# audio_pa6.net
KiCad netlist of a schematic drawn in Altium Designer
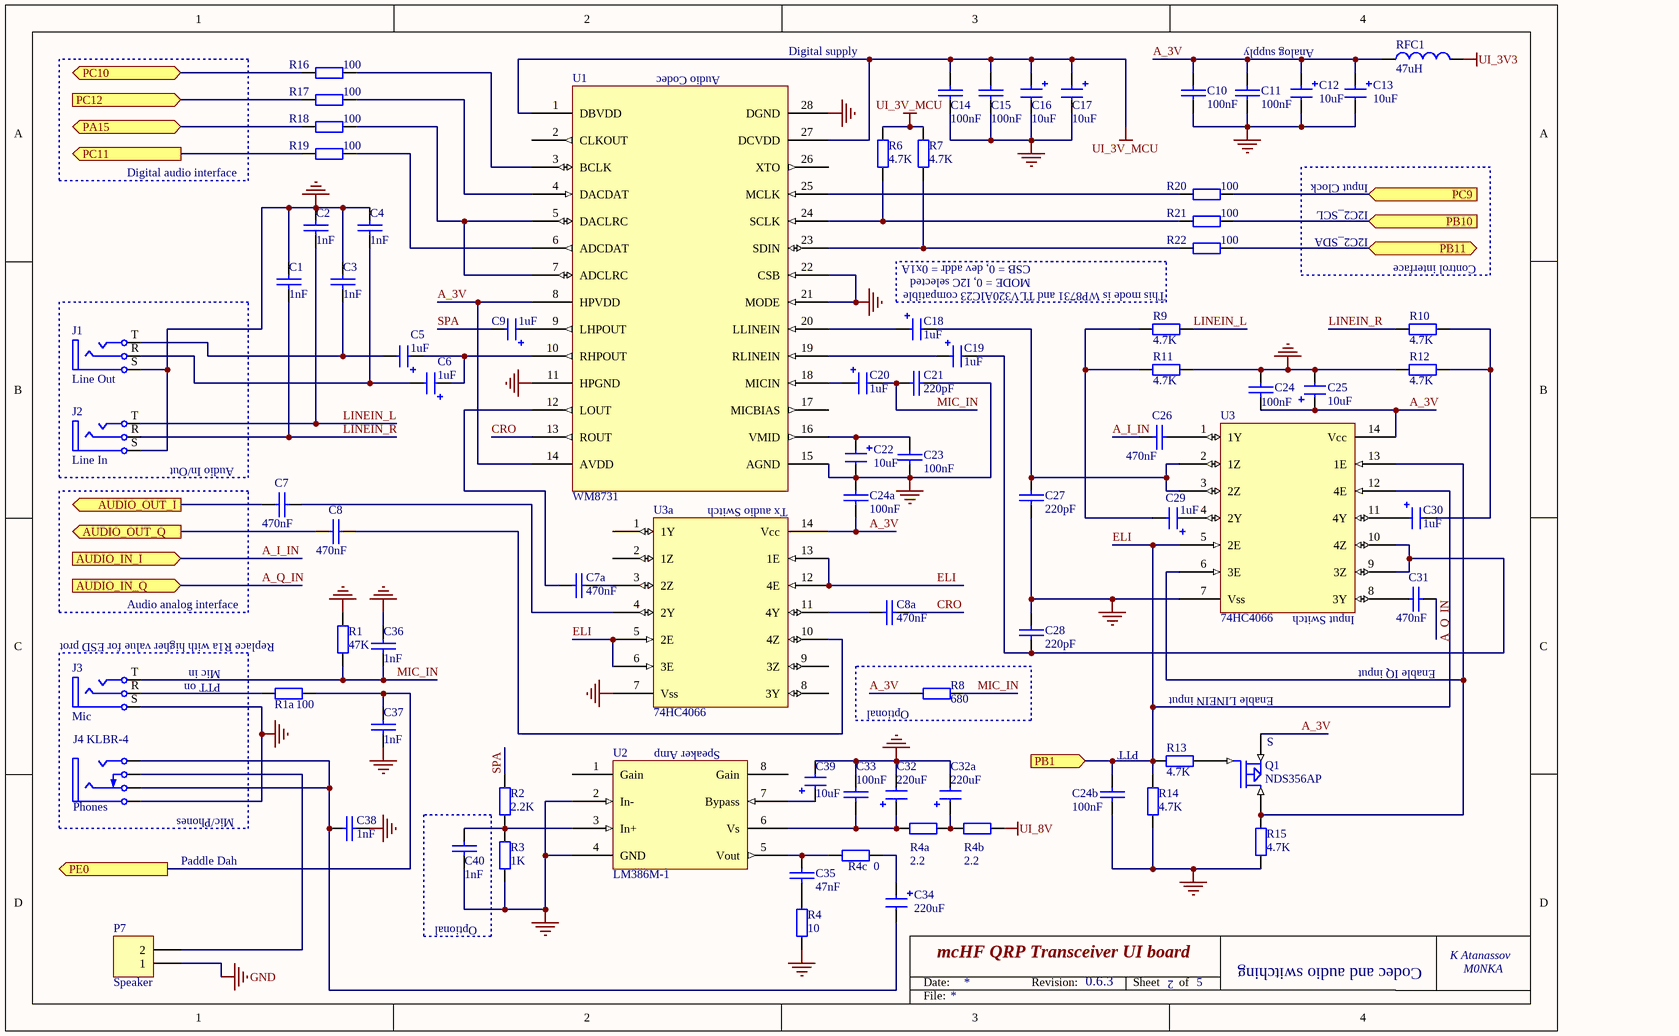
[diagram p0: audio_pa6.SchDoc]

(export (version "E")
  (design (tool "Eeschema 10.0.6"))
  (components
    (comp (ref "C1")
      (value "1nF")
      (footprint "0805-Pro")
      (description "Capacitor")
      (libsource (lib "mcHF_ui") (part "CAP"))
    )
    (comp (ref "C2")
      (value "1nF")
      (footprint "0805-Pro")
      (description "Capacitor")
      (libsource (lib "mcHF_ui") (part "CAP"))
    )
    (comp (ref "C3")
      (value "1nF")
      (footprint "0805-Pro")
      (description "Capacitor")
      (libsource (lib "mcHF_ui") (part "CAP"))
    )
    (comp (ref "C4")
      (value "1nF")
      (footprint "0805-Pro")
      (description "Capacitor")
      (libsource (lib "mcHF_ui") (part "CAP"))
    )
    (comp (ref "C5")
      (value "1uF")
      (footprint "1206_ELEC_CAP_N")
      (description "Electrolitic capacitor")
      (libsource (lib "mcHF_ui") (part "CAP-POL"))
    )
    (comp (ref "C6")
      (value "1uF")
      (footprint "1206_ELEC_CAP_N")
      (description "Electrolitic capacitor")
      (libsource (lib "mcHF_ui") (part "CAP-POL"))
    )
    (comp (ref "C7")
      (value "470nF")
      (footprint "0805-Pro")
      (description "Capacitor")
      (libsource (lib "mcHF_ui") (part "CAP"))
    )
    (comp (ref "C7a")
      (value "470nF")
      (footprint "0805-Pro")
      (description "Capacitor")
      (libsource (lib "mcHF_ui") (part "CAP"))
    )
    (comp (ref "C8")
      (value "470nF")
      (footprint "0805-Pro")
      (description "Capacitor")
      (libsource (lib "mcHF_ui") (part "CAP"))
    )
    (comp (ref "C8a")
      (value "470nF")
      (footprint "0805-Pro")
      (description "Capacitor")
      (libsource (lib "mcHF_ui") (part "CAP"))
    )
    (comp (ref "C9")
      (value "1uF")
      (footprint "1206_ELEC_CAP_N")
      (description "Electrolitic capacitor")
      (libsource (lib "mcHF_ui") (part "CAP-POL"))
    )
    (comp (ref "C10")
      (value "100nF")
      (footprint "0805-Pro")
      (description "Capacitor")
      (libsource (lib "mcHF_ui") (part "CAP"))
    )
    (comp (ref "C11")
      (value "100nF")
      (footprint "0805-Pro")
      (description "Capacitor")
      (libsource (lib "mcHF_ui") (part "CAP"))
    )
    (comp (ref "C12")
      (value "10uF")
      (footprint "1206_ELEC_CAP_N")
      (description "Electrolitic capacitor")
      (libsource (lib "mcHF_ui") (part "CAP-POL"))
    )
    (comp (ref "C13")
      (value "10uF")
      (footprint "1206_ELEC_CAP_N")
      (description "Electrolitic capacitor")
      (libsource (lib "mcHF_ui") (part "CAP-POL"))
    )
    (comp (ref "C14")
      (value "100nF")
      (footprint "0805-Pro")
      (description "Capacitor")
      (libsource (lib "mcHF_ui") (part "CAP"))
    )
    (comp (ref "C15")
      (value "100nF")
      (footprint "0805-Pro")
      (description "Capacitor")
      (libsource (lib "mcHF_ui") (part "CAP"))
    )
    (comp (ref "C16")
      (value "10uF")
      (footprint "1206_ELEC_CAP_N")
      (description "Electrolitic capacitor")
      (libsource (lib "mcHF_ui") (part "CAP-POL"))
    )
    (comp (ref "C17")
      (value "10uF")
      (footprint "1206_ELEC_CAP_N")
      (description "Electrolitic capacitor")
      (libsource (lib "mcHF_ui") (part "CAP-POL"))
    )
    (comp (ref "C18")
      (value "1uF")
      (footprint "1206_ELEC_CAP_N")
      (description "Electrolitic capacitor")
      (libsource (lib "mcHF_ui") (part "CAP-POL"))
    )
    (comp (ref "C19")
      (value "1uF")
      (footprint "1206_ELEC_CAP_N")
      (description "Electrolitic capacitor")
      (libsource (lib "mcHF_ui") (part "CAP-POL"))
    )
    (comp (ref "C20")
      (value "1uF")
      (footprint "1206_ELEC_CAP_N")
      (description "Electrolitic capacitor")
      (libsource (lib "mcHF_ui") (part "CAP-POL"))
    )
    (comp (ref "C21")
      (value "220pF")
      (footprint "0805-Pro")
      (description "Capacitor")
      (libsource (lib "mcHF_ui") (part "CAP"))
    )
    (comp (ref "C22")
      (value "10uF")
      (footprint "1206_ELEC_CAP_N")
      (description "Electrolitic capacitor")
      (libsource (lib "mcHF_ui") (part "CAP-POL"))
    )
    (comp (ref "C23")
      (value "100nF")
      (footprint "0805-Pro")
      (description "Capacitor")
      (libsource (lib "mcHF_ui") (part "CAP"))
    )
    (comp (ref "C24")
      (value "100nF")
      (footprint "0805-Pro")
      (description "Capacitor")
      (libsource (lib "mcHF_ui") (part "CAP"))
    )
    (comp (ref "C24a")
      (value "100nF")
      (footprint "0805-Pro")
      (description "Capacitor")
      (libsource (lib "mcHF_ui") (part "CAP"))
    )
    (comp (ref "C24b")
      (value "100nF")
      (footprint "0805-Pro")
      (description "Capacitor")
      (libsource (lib "mcHF_ui") (part "CAP"))
    )
    (comp (ref "C25")
      (value "10uF")
      (footprint "1206_ELEC_CAP_N")
      (description "Electrolitic capacitor")
      (libsource (lib "mcHF_ui") (part "CAP-POL"))
    )
    (comp (ref "C26")
      (value "470nF")
      (footprint "0805-Pro")
      (description "Capacitor")
      (libsource (lib "mcHF_ui") (part "CAP"))
    )
    (comp (ref "C27")
      (value "220pF")
      (footprint "0805-Pro")
      (description "Capacitor")
      (libsource (lib "mcHF_ui") (part "CAP"))
    )
    (comp (ref "C28")
      (value "220pF")
      (footprint "0805-Pro")
      (description "Capacitor")
      (libsource (lib "mcHF_ui") (part "CAP"))
    )
    (comp (ref "C29")
      (value "1uF")
      (footprint "1206_ELEC_CAP_N")
      (description "Electrolitic capacitor")
      (libsource (lib "mcHF_ui") (part "CAP-POL"))
    )
    (comp (ref "C30")
      (value "1uF")
      (footprint "1206_ELEC_CAP_N")
      (description "Electrolitic capacitor")
      (libsource (lib "mcHF_ui") (part "CAP-POL"))
    )
    (comp (ref "C31")
      (value "470nF")
      (footprint "0805-Pro")
      (description "Capacitor")
      (libsource (lib "mcHF_ui") (part "CAP"))
    )
    (comp (ref "C32")
      (value "220uF")
      (footprint "CAP_ALUM")
      (description "Electrolitic capacitor")
      (libsource (lib "mcHF_ui") (part "CAP-POL"))
    )
    (comp (ref "C32a")
      (value "220uF")
      (footprint "CAP_ALUM")
      (description "Electrolitic capacitor")
      (libsource (lib "mcHF_ui") (part "CAP-POL"))
    )
    (comp (ref "C33")
      (value "100nF")
      (footprint "0805-Pro")
      (description "Capacitor")
      (libsource (lib "mcHF_ui") (part "CAP"))
    )
    (comp (ref "C34")
      (value "220uF")
      (footprint "CAP_ALUM")
      (description "Electrolitic capacitor")
      (libsource (lib "mcHF_ui") (part "CAP-POL"))
    )
    (comp (ref "C35")
      (value "47nF")
      (footprint "0805-Pro")
      (description "Capacitor")
      (libsource (lib "mcHF_ui") (part "CAP"))
    )
    (comp (ref "C36")
      (value "1nF")
      (footprint "0805-Pro")
      (description "Capacitor")
      (libsource (lib "mcHF_ui") (part "CAP"))
    )
    (comp (ref "C37")
      (value "1nF")
      (footprint "0805-Pro")
      (description "Capacitor")
      (libsource (lib "mcHF_ui") (part "CAP"))
    )
    (comp (ref "C38")
      (value "1nF")
      (footprint "0805-Pro")
      (description "Capacitor")
      (libsource (lib "mcHF_ui") (part "CAP"))
    )
    (comp (ref "C39")
      (value "10uF")
      (footprint "1206_ELEC_CAP_N")
      (description "Electrolitic capacitor")
      (libsource (lib "mcHF_ui") (part "CAP-POL"))
    )
    (comp (ref "C40")
      (value "1nF")
      (footprint "0805-Pro")
      (description "Capacitor")
      (libsource (lib "mcHF_ui") (part "CAP"))
    )
    (comp (ref "J1")
      (value "Line Out")
      (footprint "MX-387GL_new1")
      (description "Jack Socket,Thru-Hole")
      (libsource (lib "mcHF_ui") (part "MX-387GL"))
    )
    (comp (ref "J2")
      (value "Line In")
      (footprint "MX-387GL_new1")
      (description "Jack Socket,Thru-Hole")
      (libsource (lib "mcHF_ui") (part "MX-387GL"))
    )
    (comp (ref "J3")
      (value "Mic")
      (footprint "MX-387GL_new1")
      (description "Jack Socket,Thru-Hole")
      (libsource (lib "mcHF_ui") (part "MX-387GL"))
    )
    (comp (ref "J4")
      (value "KLBR-4")
      (footprint "KLBR4")
      (description "Jack Socket 4 pin")
      (fields (field (name "FUNCTION") "Phones"))
      (libsource (lib "mcHF_ui") (part "PhoneJack"))
    )
    (comp (ref "P7")
      (value "Speaker")
      (footprint "SIP2")
      (description "Header, 2-Pin")
      (fields (field (name "CHECKED") "NA"))
      (libsource (lib "mcHF_ui") (part "Header 2"))
    )
    (comp (ref "Q1")
      (value "NDS356AP")
      (footprint "SOT-23-Pro")
      (description "MOSFET transistor")
      (libsource (lib "mcHF_ui") (part "NDS356AP"))
    )
    (comp (ref "R1")
      (value "47K")
      (footprint "0805-Pro")
      (description "Resistor")
      (libsource (lib "") (part "RES_1"))
    )
    (comp (ref "R1a")
      (value "100")
      (footprint "0805-Pro")
      (description "Resistor")
      (libsource (lib "mcHF_ui") (part "RES"))
    )
    (comp (ref "R2")
      (value "2.2K")
      (footprint "0805-Pro")
      (description "Resistor")
      (libsource (lib "") (part "RES_1"))
    )
    (comp (ref "R3")
      (value "1K")
      (footprint "0805-Pro")
      (description "Resistor")
      (libsource (lib "") (part "RES_1"))
    )
    (comp (ref "R4")
      (value "10")
      (footprint "0805-Pro")
      (description "Resistor")
      (libsource (lib "") (part "RES_1"))
    )
    (comp (ref "R4a")
      (value "2.2")
      (footprint "1206")
      (description "Resistor")
      (libsource (lib "") (part "RES_2"))
    )
    (comp (ref "R4b")
      (value "2.2")
      (footprint "1206")
      (description "Resistor")
      (libsource (lib "") (part "RES_2"))
    )
    (comp (ref "R4c")
      (value "0")
      (footprint "0805-Pro")
      (description "Resistor")
      (libsource (lib "mcHF_ui") (part "RES"))
    )
    (comp (ref "R6")
      (value "4.7K")
      (footprint "0805-Pro")
      (description "Resistor")
      (libsource (lib "") (part "RES_3"))
    )
    (comp (ref "R7")
      (value "4.7K")
      (footprint "0805-Pro")
      (description "Resistor")
      (libsource (lib "") (part "RES_3"))
    )
    (comp (ref "R8")
      (value "680")
      (footprint "0805-Pro")
      (description "Resistor")
      (libsource (lib "mcHF_ui") (part "RES"))
    )
    (comp (ref "R9")
      (value "4.7K")
      (footprint "0805-Pro")
      (description "Resistor")
      (libsource (lib "") (part "RES_2"))
    )
    (comp (ref "R10")
      (value "4.7K")
      (footprint "0805-Pro")
      (description "Resistor")
      (libsource (lib "") (part "RES_2"))
    )
    (comp (ref "R11")
      (value "4.7K")
      (footprint "0805-Pro")
      (description "Resistor")
      (libsource (lib "") (part "RES_2"))
    )
    (comp (ref "R12")
      (value "4.7K")
      (footprint "0805-Pro")
      (description "Resistor")
      (libsource (lib "") (part "RES_2"))
    )
    (comp (ref "R13")
      (value "4.7K")
      (footprint "0805-Pro")
      (description "Resistor")
      (libsource (lib "") (part "RES_2"))
    )
    (comp (ref "R14")
      (value "4.7K")
      (footprint "0805-Pro")
      (description "Resistor")
      (libsource (lib "") (part "RES_3"))
    )
    (comp (ref "R15")
      (value "4.7K")
      (footprint "0805-Pro")
      (description "Resistor")
      (libsource (lib "") (part "RES_3"))
    )
    (comp (ref "R16")
      (value "100")
      (footprint "0805-Pro")
      (description "Resistor")
      (libsource (lib "mcHF_ui") (part "RES"))
    )
    (comp (ref "R17")
      (value "100")
      (footprint "0805-Pro")
      (description "Resistor")
      (libsource (lib "mcHF_ui") (part "RES"))
    )
    (comp (ref "R18")
      (value "100")
      (footprint "0805-Pro")
      (description "Resistor")
      (libsource (lib "mcHF_ui") (part "RES"))
    )
    (comp (ref "R19")
      (value "100")
      (footprint "0805-Pro")
      (description "Resistor")
      (libsource (lib "mcHF_ui") (part "RES"))
    )
    (comp (ref "R20")
      (value "100")
      (footprint "0805-Pro")
      (description "Resistor")
      (libsource (lib "mcHF_ui") (part "RES"))
    )
    (comp (ref "R21")
      (value "100")
      (footprint "0805-Pro")
      (description "Resistor")
      (libsource (lib "mcHF_ui") (part "RES"))
    )
    (comp (ref "R22")
      (value "100")
      (footprint "0805-Pro")
      (description "Resistor")
      (libsource (lib "mcHF_ui") (part "RES"))
    )
    (comp (ref "RFC1")
      (value "47uH")
      (footprint "0805-Pro")
      (description "Inductor")
      (libsource (lib "mcHF_ui") (part "Inductor"))
    )
    (comp (ref "U1")
      (value "WM8731")
      (footprint "mcHF_ui:SSOP-28-Pro")
      (description "Audio CODEC")
      (libsource (lib "mcHF_ui") (part "WM8731"))
    )
    (comp (ref "U2")
      (value "LM386M-1")
      (footprint "mcHF_ui:SO-8-Pro")
      (description "Low Voltage Audio Power Amplifier")
      (libsource (lib "mcHF_ui") (part "LM386"))
    )
    (comp (ref "U3")
      (value "74HC4066")
      (footprint "SO-14-Pro")
      (description "Quad bilateral switch")
      (libsource (lib "mcHF_ui") (part "74HC4066"))
    )
    (comp (ref "U3a")
      (value "74HC4066")
      (footprint "SO-14-Pro")
      (description "Quad bilateral switch")
      (libsource (lib "mcHF_ui") (part "74HC4066"))
    )
  )
  (nets
    (net (code "1") (name "/AUDIO_OUT_I") (class "Default")
      (node (ref "C7") (pin "1") (pinfunction "1_1") (pintype "passive"))
    )
    (net (code "2") (name "/AUDIO_OUT_Q") (class "Default")
      (node (ref "C8") (pin "1") (pinfunction "1_1") (pintype "passive"))
    )
    (net (code "3") (name "/A_3V") (class "Default")
      (node (ref "C10") (pin "2") (pinfunction "2_2") (pintype "passive"))
      (node (ref "C11") (pin "2") (pinfunction "2_2") (pintype "passive"))
      (node (ref "C12") (pin "1") (pinfunction "1_1") (pintype "passive"))
      (node (ref "C13") (pin "1") (pinfunction "1_1") (pintype "passive"))
      (node (ref "C24") (pin "1") (pinfunction "1_1") (pintype "passive"))
      (node (ref "C24a") (pin "2") (pinfunction "2_2") (pintype "passive"))
      (node (ref "C25") (pin "1") (pinfunction "1_1") (pintype "passive"))
      (node (ref "Q1") (pin "2") (pinfunction "S_2") (pintype "input"))
      (node (ref "R8") (pin "1") (pinfunction "1_1") (pintype "passive"))
      (node (ref "RFC1") (pin "1") (pinfunction "1_1") (pintype "passive"))
      (node (ref "U1") (pin "14") (pinfunction "AVDD_14") (pintype "power_in"))
      (node (ref "U1") (pin "8") (pinfunction "HPVDD_8") (pintype "power_in"))
      (node (ref "U3") (pin "14") (pinfunction "Vcc_14") (pintype "power_in"))
      (node (ref "U3a") (pin "14") (pinfunction "Vcc_14") (pintype "power_in"))
    )
    (net (code "4") (name "/A_I_IN") (class "Default")
      (node (ref "C26") (pin "1") (pinfunction "1_1") (pintype "passive"))
    )
    (net (code "5") (name "/A_Q_IN") (class "Default")
      (node (ref "C31") (pin "2") (pinfunction "2_2") (pintype "passive"))
    )
    (net (code "6") (name "/CRO") (class "Default")
      (node (ref "C8a") (pin "2") (pinfunction "2_2") (pintype "passive"))
      (node (ref "U1") (pin "13") (pinfunction "ROUT_13") (pintype "output"))
    )
    (net (code "7") (name "/ELI") (class "Default")
      (node (ref "C24b") (pin "2") (pinfunction "2_2") (pintype "passive"))
      (node (ref "R13") (pin "2") (pinfunction "2_2") (pintype "passive"))
      (node (ref "R14") (pin "1") (pinfunction "1_1") (pintype "passive"))
      (node (ref "U3") (pin "12") (pinfunction "4E_12") (pintype "input"))
      (node (ref "U3") (pin "5") (pinfunction "2E_5") (pintype "input"))
      (node (ref "U3a") (pin "12") (pinfunction "4E_12") (pintype "input"))
      (node (ref "U3a") (pin "13") (pinfunction "1E_13") (pintype "input"))
      (node (ref "U3a") (pin "5") (pinfunction "2E_5") (pintype "input"))
      (node (ref "U3a") (pin "6") (pinfunction "3E_6") (pintype "input"))
    )
    (net (code "8") (name "/LINEIN_L") (class "Default")
      (node (ref "C2") (pin "2") (pinfunction "2_2") (pintype "passive"))
      (node (ref "J2") (pin "T") (pinfunction "1_T") (pintype "passive"))
      (node (ref "R9") (pin "1") (pinfunction "1_1") (pintype "passive"))
    )
    (net (code "9") (name "/LINEIN_R") (class "Default")
      (node (ref "C1") (pin "2") (pinfunction "2_2") (pintype "passive"))
      (node (ref "J2") (pin "R") (pinfunction "3_R") (pintype "passive"))
      (node (ref "R10") (pin "2") (pinfunction "2_2") (pintype "passive"))
    )
    (net (code "10") (name "/MIC_IN") (class "Default")
      (node (ref "C20") (pin "2") (pinfunction "2_2") (pintype "passive"))
      (node (ref "C21") (pin "2") (pinfunction "2_2") (pintype "passive"))
      (node (ref "C36") (pin "2") (pinfunction "2_2") (pintype "passive"))
      (node (ref "J3") (pin "T") (pinfunction "1_T") (pintype "passive"))
      (node (ref "R1") (pin "1") (pinfunction "1_1") (pintype "passive"))
      (node (ref "R8") (pin "2") (pinfunction "2_2") (pintype "passive"))
    )
    (net (code "11") (name "/PA15") (class "Default")
      (node (ref "R18") (pin "1") (pinfunction "1_1") (pintype "passive"))
    )
    (net (code "12") (name "/PB10") (class "Default")
      (node (ref "R21") (pin "2") (pinfunction "2_2") (pintype "passive"))
    )
    (net (code "13") (name "/PB11") (class "Default")
      (node (ref "R22") (pin "2") (pinfunction "2_2") (pintype "passive"))
    )
    (net (code "14") (name "/PC9") (class "Default")
      (node (ref "R20") (pin "2") (pinfunction "2_2") (pintype "passive"))
    )
    (net (code "15") (name "/PC10") (class "Default")
      (node (ref "R16") (pin "1") (pinfunction "1_1") (pintype "passive"))
    )
    (net (code "16") (name "/PC11") (class "Default")
      (node (ref "R19") (pin "1") (pinfunction "1_1") (pintype "passive"))
    )
    (net (code "17") (name "/PC12") (class "Default")
      (node (ref "R17") (pin "1") (pinfunction "1_1") (pintype "passive"))
    )
    (net (code "18") (name "/PE0") (class "Default")
      (node (ref "C37") (pin "1") (pinfunction "1_1") (pintype "passive"))
      (node (ref "R1a") (pin "2") (pinfunction "2_2") (pintype "passive"))
    )
    (net (code "19") (name "/SPA") (class "Default")
      (node (ref "C9") (pin "2") (pinfunction "2_2") (pintype "passive"))
      (node (ref "R2") (pin "2") (pinfunction "2_2") (pintype "passive"))
    )
    (net (code "20") (name "GND") (class "Default")
      (node (ref "C1") (pin "1") (pinfunction "1_1") (pintype "passive"))
      (node (ref "C10") (pin "1") (pinfunction "1_1") (pintype "passive"))
      (node (ref "C11") (pin "1") (pinfunction "1_1") (pintype "passive"))
      (node (ref "C12") (pin "2") (pinfunction "2_2") (pintype "passive"))
      (node (ref "C13") (pin "2") (pinfunction "2_2") (pintype "passive"))
      (node (ref "C14") (pin "1") (pinfunction "1_1") (pintype "passive"))
      (node (ref "C15") (pin "1") (pinfunction "1_1") (pintype "passive"))
      (node (ref "C16") (pin "2") (pinfunction "2_2") (pintype "passive"))
      (node (ref "C17") (pin "2") (pinfunction "2_2") (pintype "passive"))
      (node (ref "C2") (pin "1") (pinfunction "1_1") (pintype "passive"))
      (node (ref "C21") (pin "1") (pinfunction "1_1") (pintype "passive"))
      (node (ref "C22") (pin "2") (pinfunction "2_2") (pintype "passive"))
      (node (ref "C23") (pin "1") (pinfunction "1_1") (pintype "passive"))
      (node (ref "C24") (pin "2") (pinfunction "2_2") (pintype "passive"))
      (node (ref "C24a") (pin "1") (pinfunction "1_1") (pintype "passive"))
      (node (ref "C24b") (pin "1") (pinfunction "1_1") (pintype "passive"))
      (node (ref "C25") (pin "2") (pinfunction "2_2") (pintype "passive"))
      (node (ref "C27") (pin "2") (pinfunction "2_2") (pintype "passive"))
      (node (ref "C28") (pin "1") (pinfunction "1_1") (pintype "passive"))
      (node (ref "C3") (pin "1") (pinfunction "1_1") (pintype "passive"))
      (node (ref "C32") (pin "2") (pinfunction "2_2") (pintype "passive"))
      (node (ref "C32a") (pin "2") (pinfunction "2_2") (pintype "passive"))
      (node (ref "C33") (pin "2") (pinfunction "2_2") (pintype "passive"))
      (node (ref "C36") (pin "1") (pinfunction "1_1") (pintype "passive"))
      (node (ref "C37") (pin "2") (pinfunction "2_2") (pintype "passive"))
      (node (ref "C38") (pin "2") (pinfunction "2_2") (pintype "passive"))
      (node (ref "C39") (pin "2") (pinfunction "2_2") (pintype "passive"))
      (node (ref "C4") (pin "1") (pinfunction "1_1") (pintype "passive"))
      (node (ref "C40") (pin "1") (pinfunction "1_1") (pintype "passive"))
      (node (ref "J1") (pin "S") (pinfunction "2_S") (pintype "power_in"))
      (node (ref "J2") (pin "S") (pinfunction "2_S") (pintype "power_in"))
      (node (ref "J3") (pin "S") (pinfunction "2_S") (pintype "power_in"))
      (node (ref "J4") (pin "S") (pinfunction "S_S") (pintype "power_in"))
      (node (ref "P7") (pin "1") (pinfunction "1_1") (pintype "passive"))
      (node (ref "R1") (pin "2") (pinfunction "2_2") (pintype "passive"))
      (node (ref "R11") (pin "1") (pinfunction "1_1") (pintype "passive"))
      (node (ref "R12") (pin "2") (pinfunction "2_2") (pintype "passive"))
      (node (ref "R14") (pin "2") (pinfunction "2_2") (pintype "passive"))
      (node (ref "R15") (pin "2") (pinfunction "2_2") (pintype "passive"))
      (node (ref "R3") (pin "1") (pinfunction "1_1") (pintype "passive"))
      (node (ref "R4") (pin "1") (pinfunction "1_1") (pintype "passive"))
      (node (ref "U1") (pin "11") (pinfunction "HPGND_11") (pintype "power_in"))
      (node (ref "U1") (pin "15") (pinfunction "AGND_15") (pintype "power_in"))
      (node (ref "U1") (pin "21") (pinfunction "MODE_21") (pintype "input"))
      (node (ref "U1") (pin "22") (pinfunction "CSB_22") (pintype "input"))
      (node (ref "U1") (pin "28") (pinfunction "DGND_28") (pintype "power_in"))
      (node (ref "U2") (pin "2") (pinfunction "In-_2") (pintype "input"))
      (node (ref "U2") (pin "4") (pinfunction "GND_4") (pintype "power_in"))
      (node (ref "U3") (pin "7") (pinfunction "Vss_7") (pintype "power_in"))
      (node (ref "U3a") (pin "7") (pinfunction "Vss_7") (pintype "power_in"))
    )
    (net (code "21") (name "Net-(C29-Pad2)") (class "Default")
      (node (ref "C29") (pin "2") (pinfunction "2_2") (pintype "passive"))
      (node (ref "R11") (pin "2") (pinfunction "2_2") (pintype "passive"))
      (node (ref "R9") (pin "2") (pinfunction "2_2") (pintype "passive"))
    )
    (net (code "22") (name "Net-(C30-Pad2)") (class "Default")
      (node (ref "C30") (pin "2") (pinfunction "2_2") (pintype "passive"))
      (node (ref "R10") (pin "1") (pinfunction "1_1") (pintype "passive"))
      (node (ref "R12") (pin "1") (pinfunction "1_1") (pintype "passive"))
    )
    (net (code "23") (name "Net-(C32a-Pad1)") (class "Default")
      (node (ref "C32a") (pin "1") (pinfunction "1_1") (pintype "passive"))
      (node (ref "R4a") (pin "1") (pinfunction "1_1") (pintype "passive"))
      (node (ref "R4b") (pin "2") (pinfunction "2_2") (pintype "passive"))
    )
    (net (code "24") (name "Net-(C34-Pad1)") (class "Default")
      (node (ref "C34") (pin "1") (pinfunction "1_1") (pintype "passive"))
      (node (ref "R4c") (pin "2") (pinfunction "2_2") (pintype "passive"))
    )
    (net (code "25") (name "Net-(C34-Pad2)") (class "Default")
      (node (ref "C34") (pin "2") (pinfunction "2_2") (pintype "passive"))
      (node (ref "C38") (pin "1") (pinfunction "1_1") (pintype "passive"))
      (node (ref "J4") (pin "R") (pinfunction "R_R") (pintype "passive"))
      (node (ref "J4") (pin "T") (pinfunction "T_T") (pintype "passive"))
    )
    (net (code "26") (name "Net-(C35-Pad1)") (class "Default")
      (node (ref "C35") (pin "1") (pinfunction "1_1") (pintype "passive"))
      (node (ref "R4") (pin "2") (pinfunction "2_2") (pintype "passive"))
    )
    (net (code "27") (name "Net-(J1-1)") (class "Default")
      (node (ref "C3") (pin "2") (pinfunction "2_2") (pintype "passive"))
      (node (ref "C5") (pin "2") (pinfunction "2_2") (pintype "passive"))
      (node (ref "J1") (pin "T") (pinfunction "1_T") (pintype "passive"))
    )
    (net (code "28") (name "Net-(J1-3)") (class "Default")
      (node (ref "C4") (pin "2") (pinfunction "2_2") (pintype "passive"))
      (node (ref "C6") (pin "2") (pinfunction "2_2") (pintype "passive"))
      (node (ref "J1") (pin "R") (pinfunction "3_R") (pintype "passive"))
    )
    (net (code "29") (name "Net-(J3-3)") (class "Default")
      (node (ref "J3") (pin "R") (pinfunction "3_R") (pintype "passive"))
      (node (ref "R1a") (pin "1") (pinfunction "1_1") (pintype "passive"))
    )
    (net (code "30") (name "Net-(J4-PadB)") (class "Default")
      (node (ref "J4") (pin "B") (pinfunction "B_B") (pintype "passive"))
      (node (ref "P7") (pin "2") (pinfunction "2_2") (pintype "passive"))
    )
    (net (code "31") (name "Net-(Q1-D)") (class "Default")
      (node (ref "Q1") (pin "3") (pinfunction "D_3") (pintype "input"))
      (node (ref "R15") (pin "1") (pinfunction "1_1") (pintype "passive"))
      (node (ref "U3") (pin "13") (pinfunction "1E_13") (pintype "input"))
      (node (ref "U3") (pin "6") (pinfunction "3E_6") (pintype "input"))
    )
    (net (code "32") (name "Net-(Q1-G)") (class "Default")
      (node (ref "Q1") (pin "1") (pinfunction "G_1") (pintype "input"))
      (node (ref "R13") (pin "1") (pinfunction "1_1") (pintype "passive"))
    )
    (net (code "33") (name "Net-(U1-ADCDAT)") (class "Default")
      (node (ref "R19") (pin "2") (pinfunction "2_2") (pintype "passive"))
      (node (ref "U1") (pin "6") (pinfunction "ADCDAT_6") (pintype "output"))
    )
    (net (code "34") (name "Net-(U1-ADCLRC)") (class "Default")
      (node (ref "R18") (pin "2") (pinfunction "2_2") (pintype "passive"))
      (node (ref "U1") (pin "5") (pinfunction "DACLRC_5") (pintype "bidirectional"))
      (node (ref "U1") (pin "7") (pinfunction "ADCLRC_7") (pintype "bidirectional"))
    )
    (net (code "35") (name "Net-(U1-BCLK)") (class "Default")
      (node (ref "R16") (pin "2") (pinfunction "2_2") (pintype "passive"))
      (node (ref "U1") (pin "3") (pinfunction "BCLK_3") (pintype "bidirectional"))
    )
    (net (code "36") (name "Net-(U1-DACDAT)") (class "Default")
      (node (ref "R17") (pin "2") (pinfunction "2_2") (pintype "passive"))
      (node (ref "U1") (pin "4") (pinfunction "DACDAT_4") (pintype "input"))
    )
    (net (code "37") (name "Net-(U1-LHPOUT)") (class "Default")
      (node (ref "C9") (pin "1") (pinfunction "1_1") (pintype "passive"))
      (node (ref "U1") (pin "9") (pinfunction "LHPOUT_9") (pintype "output"))
    )
    (net (code "38") (name "Net-(U1-LLINEIN)") (class "Default")
      (node (ref "C18") (pin "1") (pinfunction "1_1") (pintype "passive"))
      (node (ref "U1") (pin "20") (pinfunction "LLINEIN_20") (pintype "input"))
    )
    (net (code "39") (name "Net-(U1-LOUT)") (class "Default")
      (node (ref "C7a") (pin "1") (pinfunction "1_1") (pintype "passive"))
      (node (ref "U1") (pin "12") (pinfunction "LOUT_12") (pintype "output"))
    )
    (net (code "40") (name "Net-(U1-MCLK)") (class "Default")
      (node (ref "R20") (pin "1") (pinfunction "1_1") (pintype "passive"))
      (node (ref "U1") (pin "25") (pinfunction "MCLK_25") (pintype "input"))
    )
    (net (code "41") (name "Net-(U1-MICIN)") (class "Default")
      (node (ref "C20") (pin "1") (pinfunction "1_1") (pintype "passive"))
      (node (ref "U1") (pin "18") (pinfunction "MICIN_18") (pintype "input"))
    )
    (net (code "42") (name "Net-(U1-RHPOUT)") (class "Default")
      (node (ref "C5") (pin "1") (pinfunction "1_1") (pintype "passive"))
      (node (ref "C6") (pin "1") (pinfunction "1_1") (pintype "passive"))
      (node (ref "U1") (pin "10") (pinfunction "RHPOUT_10") (pintype "output"))
    )
    (net (code "43") (name "Net-(U1-RLINEIN)") (class "Default")
      (node (ref "C19") (pin "1") (pinfunction "1_1") (pintype "passive"))
      (node (ref "U1") (pin "19") (pinfunction "RLINEIN_19") (pintype "input"))
    )
    (net (code "44") (name "Net-(U1-SCLK)") (class "Default")
      (node (ref "R21") (pin "1") (pinfunction "1_1") (pintype "passive"))
      (node (ref "R6") (pin "2") (pinfunction "2_2") (pintype "passive"))
      (node (ref "U1") (pin "24") (pinfunction "SCLK_24") (pintype "input"))
    )
    (net (code "45") (name "Net-(U1-SDIN)") (class "Default")
      (node (ref "R22") (pin "1") (pinfunction "1_1") (pintype "passive"))
      (node (ref "R7") (pin "2") (pinfunction "2_2") (pintype "passive"))
      (node (ref "U1") (pin "23") (pinfunction "SDIN_23") (pintype "bidirectional"))
    )
    (net (code "46") (name "Net-(U1-VMID)") (class "Default")
      (node (ref "C22") (pin "1") (pinfunction "1_1") (pintype "passive"))
      (node (ref "C23") (pin "2") (pinfunction "2_2") (pintype "passive"))
      (node (ref "U1") (pin "16") (pinfunction "VMID_16") (pintype "output"))
    )
    (net (code "47") (name "Net-(U2-Bypass)") (class "Default")
      (node (ref "C39") (pin "1") (pinfunction "1_1") (pintype "passive"))
      (node (ref "U2") (pin "7") (pinfunction "Bypass_7") (pintype "input"))
    )
    (net (code "48") (name "Net-(U2-In+)") (class "Default")
      (node (ref "C40") (pin "2") (pinfunction "2_2") (pintype "passive"))
      (node (ref "R2") (pin "1") (pinfunction "1_1") (pintype "passive"))
      (node (ref "R3") (pin "2") (pinfunction "2_2") (pintype "passive"))
      (node (ref "U2") (pin "3") (pinfunction "In+_3") (pintype "input"))
    )
    (net (code "49") (name "Net-(U2-Vout)") (class "Default")
      (node (ref "C35") (pin "2") (pinfunction "2_2") (pintype "passive"))
      (node (ref "R4c") (pin "1") (pinfunction "1_1") (pintype "passive"))
      (node (ref "U2") (pin "5") (pinfunction "Vout_5") (pintype "output"))
    )
    (net (code "50") (name "Net-(U2-Vs)") (class "Default")
      (node (ref "C32") (pin "1") (pinfunction "1_1") (pintype "passive"))
      (node (ref "C33") (pin "1") (pinfunction "1_1") (pintype "passive"))
      (node (ref "R4a") (pin "2") (pinfunction "2_2") (pintype "passive"))
      (node (ref "U2") (pin "6") (pinfunction "Vs_6") (pintype "power_in"))
    )
    (net (code "51") (name "Net-(U3-1Y)") (class "Default")
      (node (ref "C26") (pin "2") (pinfunction "2_2") (pintype "passive"))
      (node (ref "U3") (pin "1") (pinfunction "1Y_1") (pintype "bidirectional"))
    )
    (net (code "52") (name "Net-(U3-1Z)") (class "Default")
      (node (ref "C18") (pin "2") (pinfunction "2_2") (pintype "passive"))
      (node (ref "C27") (pin "1") (pinfunction "1_1") (pintype "passive"))
      (node (ref "U3") (pin "2") (pinfunction "1Z_2") (pintype "bidirectional"))
      (node (ref "U3") (pin "3") (pinfunction "2Z_3") (pintype "bidirectional"))
    )
    (net (code "53") (name "Net-(U3-2Y)") (class "Default")
      (node (ref "C29") (pin "1") (pinfunction "1_1") (pintype "passive"))
      (node (ref "U3") (pin "4") (pinfunction "2Y_4") (pintype "bidirectional"))
    )
    (net (code "54") (name "Net-(U3-3Y)") (class "Default")
      (node (ref "C31") (pin "1") (pinfunction "1_1") (pintype "passive"))
      (node (ref "U3") (pin "8") (pinfunction "3Y_8") (pintype "bidirectional"))
    )
    (net (code "55") (name "Net-(U3-3Z)") (class "Default")
      (node (ref "C19") (pin "2") (pinfunction "2_2") (pintype "passive"))
      (node (ref "C28") (pin "2") (pinfunction "2_2") (pintype "passive"))
      (node (ref "U3") (pin "10") (pinfunction "4Z_10") (pintype "bidirectional"))
      (node (ref "U3") (pin "9") (pinfunction "3Z_9") (pintype "bidirectional"))
    )
    (net (code "56") (name "Net-(U3-4Y)") (class "Default")
      (node (ref "C30") (pin "1") (pinfunction "1_1") (pintype "passive"))
      (node (ref "U3") (pin "11") (pinfunction "4Y_11") (pintype "bidirectional"))
    )
    (net (code "57") (name "Net-(U3a-2Y)") (class "Default")
      (node (ref "C7") (pin "2") (pinfunction "2_2") (pintype "passive"))
      (node (ref "U3a") (pin "4") (pinfunction "2Y_4") (pintype "bidirectional"))
    )
    (net (code "58") (name "Net-(U3a-2Z)") (class "Default")
      (node (ref "C7a") (pin "2") (pinfunction "2_2") (pintype "passive"))
      (node (ref "U3a") (pin "3") (pinfunction "2Z_3") (pintype "bidirectional"))
    )
    (net (code "59") (name "Net-(U3a-4Y)") (class "Default")
      (node (ref "C8a") (pin "1") (pinfunction "1_1") (pintype "passive"))
      (node (ref "U3a") (pin "11") (pinfunction "4Y_11") (pintype "bidirectional"))
    )
    (net (code "60") (name "Net-(U3a-4Z)") (class "Default")
      (node (ref "C8") (pin "2") (pinfunction "2_2") (pintype "passive"))
      (node (ref "U3a") (pin "10") (pinfunction "4Z_10") (pintype "bidirectional"))
    )
    (net (code "61") (name "UI_3V3") (class "Default")
      (node (ref "RFC1") (pin "2") (pinfunction "2_2") (pintype "passive"))
    )
    (net (code "62") (name "UI_3V_MCU") (class "Default")
      (node (ref "C14") (pin "2") (pinfunction "2_2") (pintype "passive"))
      (node (ref "C15") (pin "2") (pinfunction "2_2") (pintype "passive"))
      (node (ref "C16") (pin "1") (pinfunction "1_1") (pintype "passive"))
      (node (ref "C17") (pin "1") (pinfunction "1_1") (pintype "passive"))
      (node (ref "R6") (pin "1") (pinfunction "1_1") (pintype "passive"))
      (node (ref "R7") (pin "1") (pinfunction "1_1") (pintype "passive"))
      (node (ref "U1") (pin "1") (pinfunction "DBVDD_1") (pintype "power_in"))
      (node (ref "U1") (pin "27") (pinfunction "DCVDD_27") (pintype "power_in"))
    )
    (net (code "63") (name "UI_8V") (class "Default")
      (node (ref "R4b") (pin "1") (pinfunction "1_1") (pintype "passive"))
    )
    (net (code "64") (name "unconnected-(U1-CLKOUT-Pad2)") (class "Default")
      (node (ref "U1") (pin "2") (pinfunction "CLKOUT_2") (pintype "output"))
    )
    (net (code "65") (name "unconnected-(U1-MICBIAS-Pad17)") (class "Default")
      (node (ref "U1") (pin "17") (pinfunction "MICBIAS_17") (pintype "output"))
    )
    (net (code "66") (name "unconnected-(U1-XTO-Pad26)") (class "Default")
      (node (ref "U1") (pin "26") (pinfunction "XTO_26") (pintype "output"))
    )
    (net (code "67") (name "unconnected-(U2-Gain-Pad1)") (class "Default")
      (node (ref "U2") (pin "1") (pinfunction "Gain_1") (pintype "passive"))
    )
    (net (code "68") (name "unconnected-(U2-Gain-Pad8)") (class "Default")
      (node (ref "U2") (pin "8") (pinfunction "Gain_8") (pintype "passive"))
    )
    (net (code "69") (name "unconnected-(U3a-1Y-Pad1)") (class "Default")
      (node (ref "U3a") (pin "1") (pinfunction "1Y_1") (pintype "bidirectional"))
    )
    (net (code "70") (name "unconnected-(U3a-1Z-Pad2)") (class "Default")
      (node (ref "U3a") (pin "2") (pinfunction "1Z_2") (pintype "bidirectional"))
    )
    (net (code "71") (name "unconnected-(U3a-3Y-Pad8)") (class "Default")
      (node (ref "U3a") (pin "8") (pinfunction "3Y_8") (pintype "bidirectional"))
    )
    (net (code "72") (name "unconnected-(U3a-3Z-Pad9)") (class "Default")
      (node (ref "U3a") (pin "9") (pinfunction "3Z_9") (pintype "bidirectional"))
    )
  )
)
